# K-Diag_small-_single_small-multi2.net
KiCad netlist of a schematic drawn in EAGLE
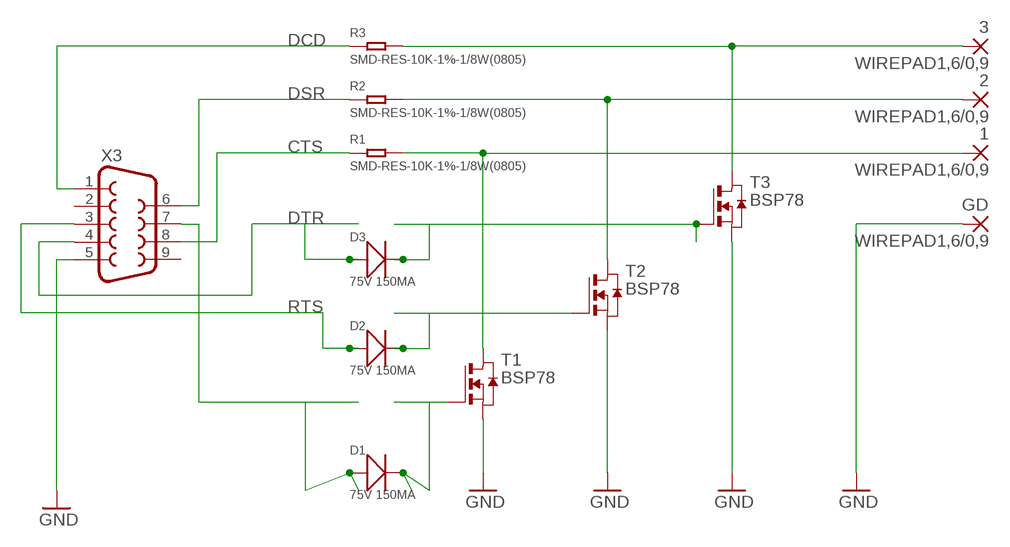
[diagram p0: schematic, sheet 1]
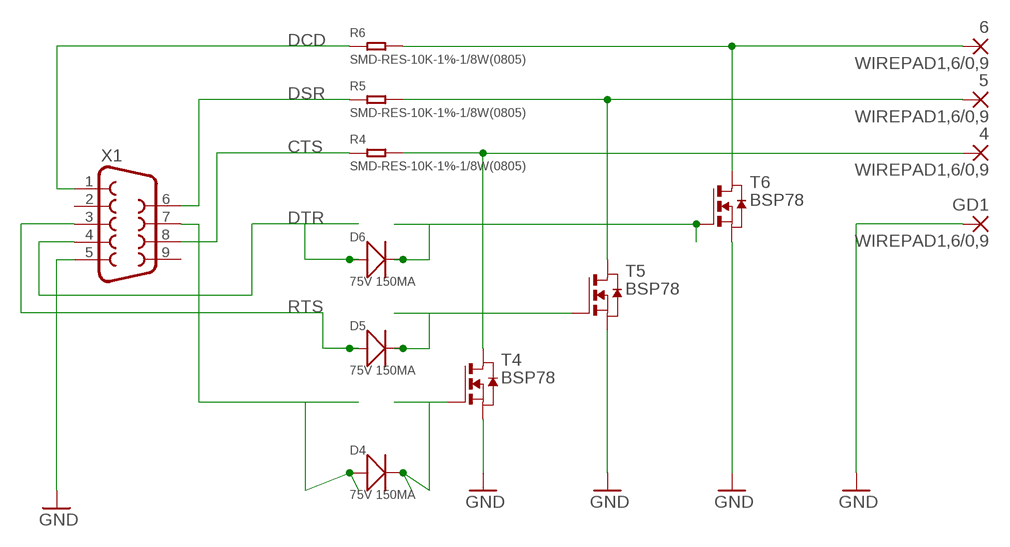
[diagram p1: schematic, sheet 2]
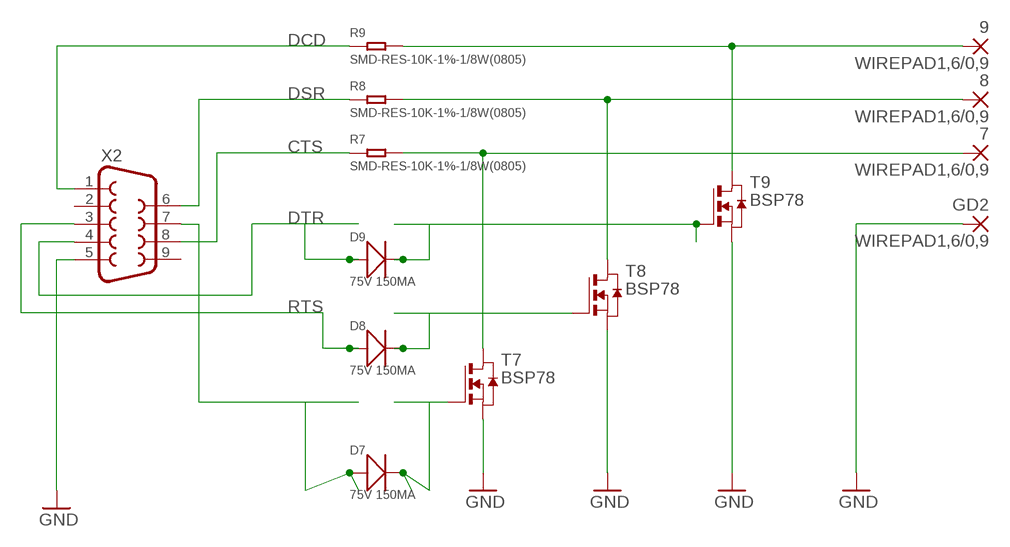
[diagram p2: schematic, sheet 3]
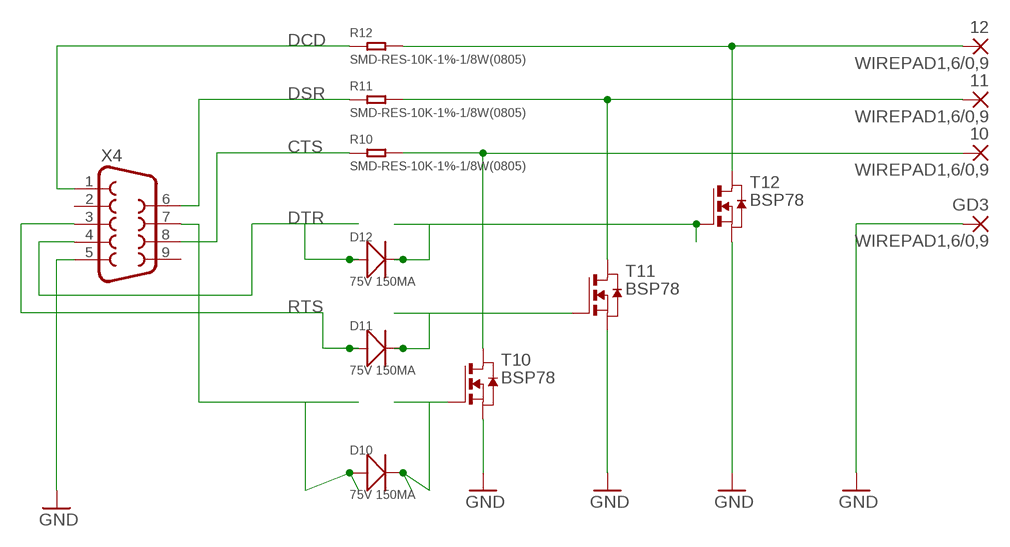
[diagram p3: schematic, sheet 4]
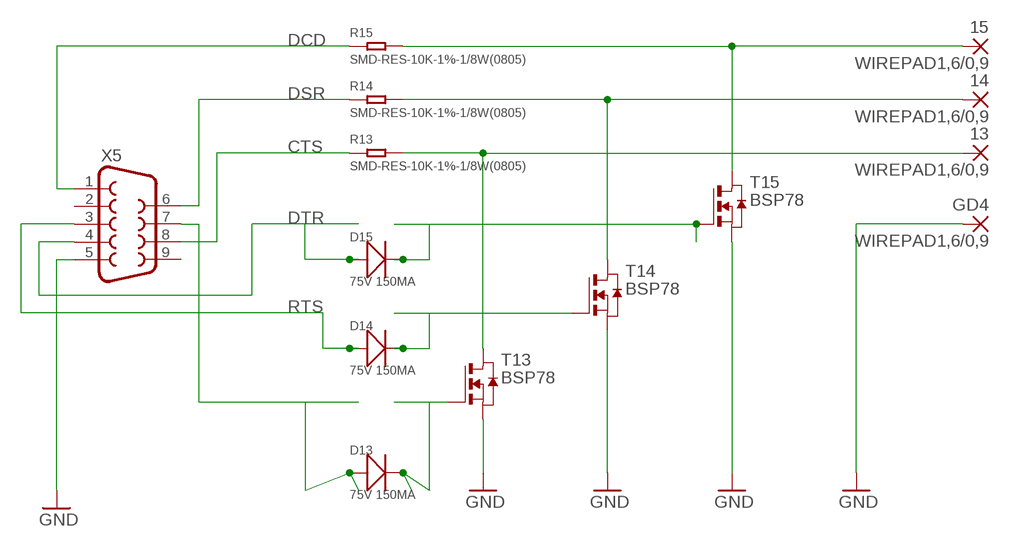
[diagram p4: schematic, sheet 5]
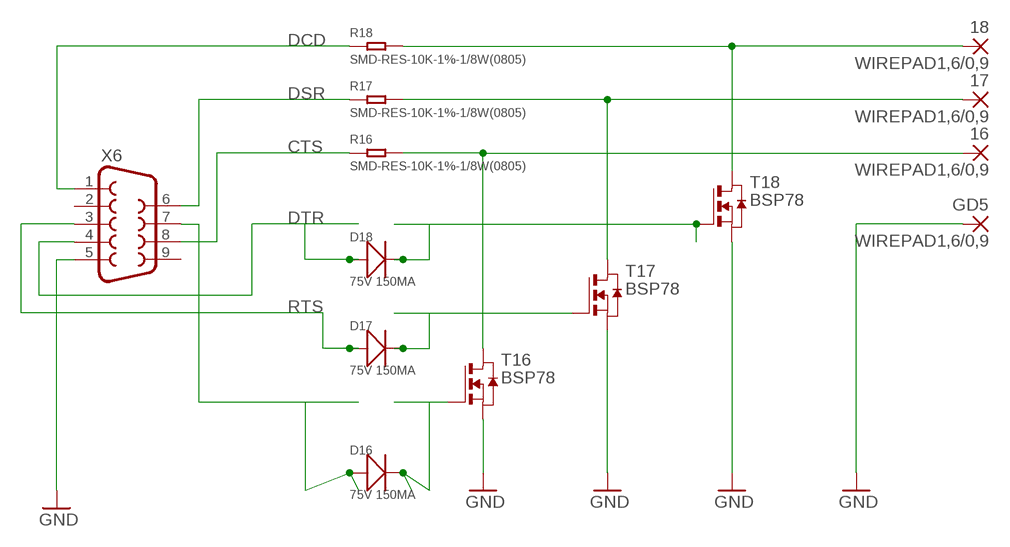
[diagram p5: schematic, sheet 6]
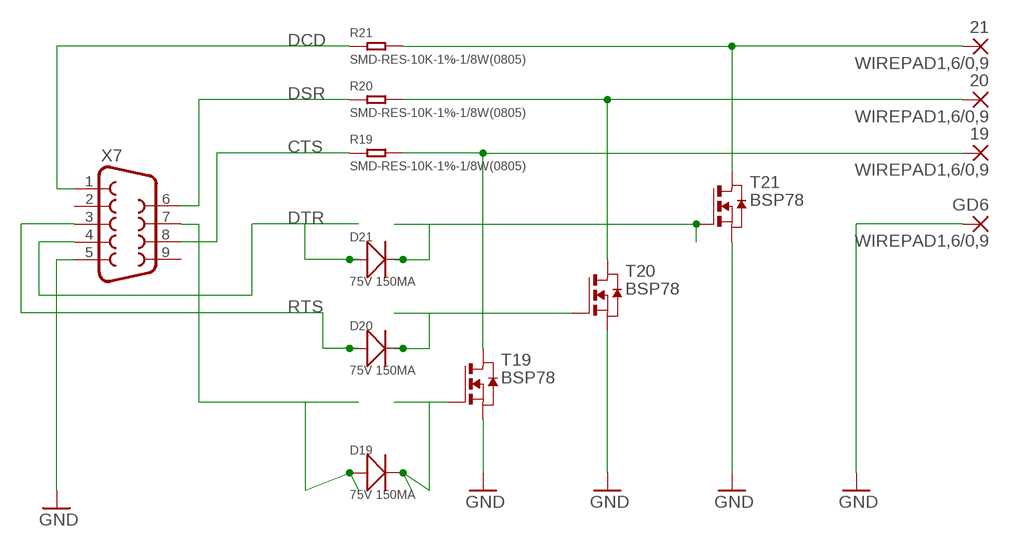
[diagram p6: schematic, sheet 7]
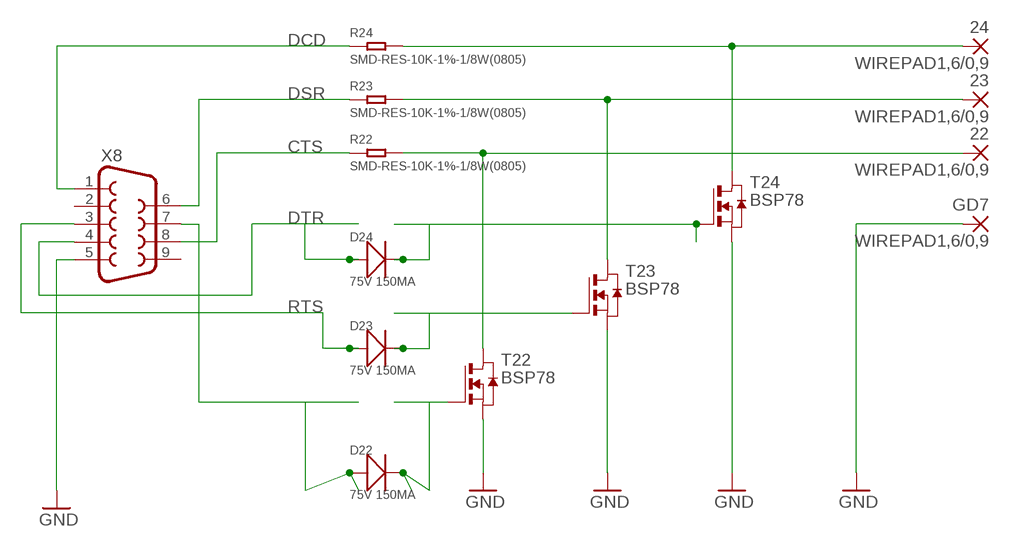
[diagram p7: schematic, sheet 8]
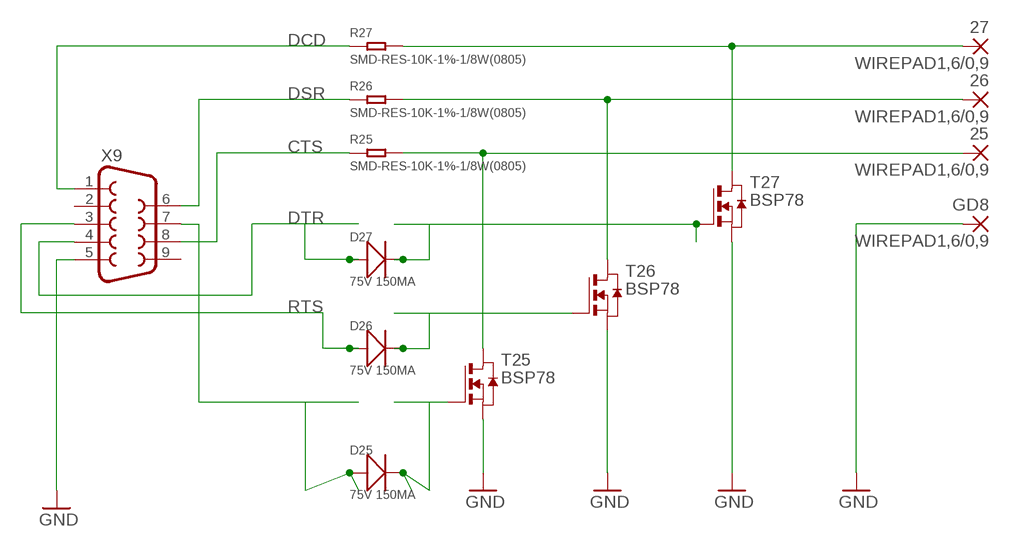
[diagram p8: schematic, sheet 9]

(export (version "E")
  (design (tool "Eeschema 10.0.6"))
  (components
    (comp (ref "4")
      (value "WIREPAD1,6/0,9")
      (footprint "eagle-import:1,6_0,9")
      (libsource (lib "eagle-import") (part "WIREPAD1,6/0,9"))
    )
    (comp (ref "5")
      (value "WIREPAD1,6/0,9")
      (footprint "eagle-import:1,6_0,9")
      (libsource (lib "eagle-import") (part "WIREPAD1,6/0,9"))
    )
    (comp (ref "6")
      (value "WIREPAD1,6/0,9")
      (footprint "eagle-import:1,6_0,9")
      (libsource (lib "eagle-import") (part "WIREPAD1,6/0,9"))
    )
    (comp (ref "D4")
      (value "75V 150MA")
      (footprint "eagle-import:LED-1206")
      (fields (field (name "MPN") "CD1206-S01575"))
      (libsource (lib "eagle-import") (part "SMD-DIODE-SWITCHING-75V-150MA(D1206)"))
    )
    (comp (ref "D5")
      (value "75V 150MA")
      (footprint "eagle-import:LED-1206")
      (fields (field (name "MPN") "CD1206-S01575"))
      (libsource (lib "eagle-import") (part "SMD-DIODE-SWITCHING-75V-150MA(D1206)"))
    )
    (comp (ref "D6")
      (value "75V 150MA")
      (footprint "eagle-import:LED-1206")
      (fields (field (name "MPN") "CD1206-S01575"))
      (libsource (lib "eagle-import") (part "SMD-DIODE-SWITCHING-75V-150MA(D1206)"))
    )
    (comp (ref "GD1")
      (value "WIREPAD1,6/0,9")
      (footprint "eagle-import:1,6_0,9")
      (libsource (lib "eagle-import") (part "WIREPAD1,6/0,9"))
    )
    (comp (ref "R4")
      (value "SMD-RES-10K-1%-1/8W(0805)")
      (footprint "eagle-import:R0805")
      (fields (field (name "MPN") "RC0805FR-0710KL"))
      (libsource (lib "eagle-import") (part "SMD-RES-10K-1%-1/8W(0805)"))
    )
    (comp (ref "R5")
      (value "SMD-RES-10K-1%-1/8W(0805)")
      (footprint "eagle-import:R0805")
      (fields (field (name "MPN") "RC0805FR-0710KL"))
      (libsource (lib "eagle-import") (part "SMD-RES-10K-1%-1/8W(0805)"))
    )
    (comp (ref "R6")
      (value "SMD-RES-10K-1%-1/8W(0805)")
      (footprint "eagle-import:R0805")
      (fields (field (name "MPN") "RC0805FR-0710KL"))
      (libsource (lib "eagle-import") (part "SMD-RES-10K-1%-1/8W(0805)"))
    )
    (comp (ref "T4")
      (value "BSP78")
      (footprint "eagle-import:SOT223")
      (libsource (lib "eagle-import") (part "NMOSSOT223"))
    )
    (comp (ref "T5")
      (value "BSP78")
      (footprint "eagle-import:SOT223")
      (libsource (lib "eagle-import") (part "NMOSSOT223"))
    )
    (comp (ref "T6")
      (value "BSP78")
      (footprint "eagle-import:SOT223")
      (libsource (lib "eagle-import") (part "NMOSSOT223"))
    )
    (comp (ref "X1")
      (value "F09D")
      (footprint "eagle-import:F09D")
      (libsource (lib "eagle-import") (part "F09D"))
    )
    (comp (ref "16")
      (value "WIREPAD1,6/0,9")
      (footprint "eagle-import:1,6_0,9")
      (libsource (lib "eagle-import") (part "WIREPAD1,6/0,9"))
    )
    (comp (ref "17")
      (value "WIREPAD1,6/0,9")
      (footprint "eagle-import:1,6_0,9")
      (libsource (lib "eagle-import") (part "WIREPAD1,6/0,9"))
    )
    (comp (ref "18")
      (value "WIREPAD1,6/0,9")
      (footprint "eagle-import:1,6_0,9")
      (libsource (lib "eagle-import") (part "WIREPAD1,6/0,9"))
    )
    (comp (ref "D16")
      (value "75V 150MA")
      (footprint "eagle-import:LED-1206")
      (fields (field (name "MPN") "CD1206-S01575"))
      (libsource (lib "eagle-import") (part "SMD-DIODE-SWITCHING-75V-150MA(D1206)"))
    )
    (comp (ref "D17")
      (value "75V 150MA")
      (footprint "eagle-import:LED-1206")
      (fields (field (name "MPN") "CD1206-S01575"))
      (libsource (lib "eagle-import") (part "SMD-DIODE-SWITCHING-75V-150MA(D1206)"))
    )
    (comp (ref "D18")
      (value "75V 150MA")
      (footprint "eagle-import:LED-1206")
      (fields (field (name "MPN") "CD1206-S01575"))
      (libsource (lib "eagle-import") (part "SMD-DIODE-SWITCHING-75V-150MA(D1206)"))
    )
    (comp (ref "GD5")
      (value "WIREPAD1,6/0,9")
      (footprint "eagle-import:1,6_0,9")
      (libsource (lib "eagle-import") (part "WIREPAD1,6/0,9"))
    )
    (comp (ref "R16")
      (value "SMD-RES-10K-1%-1/8W(0805)")
      (footprint "eagle-import:R0805")
      (fields (field (name "MPN") "RC0805FR-0710KL"))
      (libsource (lib "eagle-import") (part "SMD-RES-10K-1%-1/8W(0805)"))
    )
    (comp (ref "R17")
      (value "SMD-RES-10K-1%-1/8W(0805)")
      (footprint "eagle-import:R0805")
      (fields (field (name "MPN") "RC0805FR-0710KL"))
      (libsource (lib "eagle-import") (part "SMD-RES-10K-1%-1/8W(0805)"))
    )
    (comp (ref "R18")
      (value "SMD-RES-10K-1%-1/8W(0805)")
      (footprint "eagle-import:R0805")
      (fields (field (name "MPN") "RC0805FR-0710KL"))
      (libsource (lib "eagle-import") (part "SMD-RES-10K-1%-1/8W(0805)"))
    )
    (comp (ref "T16")
      (value "BSP78")
      (footprint "eagle-import:SOT223")
      (libsource (lib "eagle-import") (part "NMOSSOT223"))
    )
    (comp (ref "T17")
      (value "BSP78")
      (footprint "eagle-import:SOT223")
      (libsource (lib "eagle-import") (part "NMOSSOT223"))
    )
    (comp (ref "T18")
      (value "BSP78")
      (footprint "eagle-import:SOT223")
      (libsource (lib "eagle-import") (part "NMOSSOT223"))
    )
    (comp (ref "X6")
      (value "F09D")
      (footprint "eagle-import:F09D")
      (libsource (lib "eagle-import") (part "F09D"))
    )
    (comp (ref "13")
      (value "WIREPAD1,6/0,9")
      (footprint "eagle-import:1,6_0,9")
      (libsource (lib "eagle-import") (part "WIREPAD1,6/0,9"))
    )
    (comp (ref "14")
      (value "WIREPAD1,6/0,9")
      (footprint "eagle-import:1,6_0,9")
      (libsource (lib "eagle-import") (part "WIREPAD1,6/0,9"))
    )
    (comp (ref "15")
      (value "WIREPAD1,6/0,9")
      (footprint "eagle-import:1,6_0,9")
      (libsource (lib "eagle-import") (part "WIREPAD1,6/0,9"))
    )
    (comp (ref "D13")
      (value "75V 150MA")
      (footprint "eagle-import:LED-1206")
      (fields (field (name "MPN") "CD1206-S01575"))
      (libsource (lib "eagle-import") (part "SMD-DIODE-SWITCHING-75V-150MA(D1206)"))
    )
    (comp (ref "D14")
      (value "75V 150MA")
      (footprint "eagle-import:LED-1206")
      (fields (field (name "MPN") "CD1206-S01575"))
      (libsource (lib "eagle-import") (part "SMD-DIODE-SWITCHING-75V-150MA(D1206)"))
    )
    (comp (ref "D15")
      (value "75V 150MA")
      (footprint "eagle-import:LED-1206")
      (fields (field (name "MPN") "CD1206-S01575"))
      (libsource (lib "eagle-import") (part "SMD-DIODE-SWITCHING-75V-150MA(D1206)"))
    )
    (comp (ref "GD4")
      (value "WIREPAD1,6/0,9")
      (footprint "eagle-import:1,6_0,9")
      (libsource (lib "eagle-import") (part "WIREPAD1,6/0,9"))
    )
    (comp (ref "R13")
      (value "SMD-RES-10K-1%-1/8W(0805)")
      (footprint "eagle-import:R0805")
      (fields (field (name "MPN") "RC0805FR-0710KL"))
      (libsource (lib "eagle-import") (part "SMD-RES-10K-1%-1/8W(0805)"))
    )
    (comp (ref "R14")
      (value "SMD-RES-10K-1%-1/8W(0805)")
      (footprint "eagle-import:R0805")
      (fields (field (name "MPN") "RC0805FR-0710KL"))
      (libsource (lib "eagle-import") (part "SMD-RES-10K-1%-1/8W(0805)"))
    )
    (comp (ref "R15")
      (value "SMD-RES-10K-1%-1/8W(0805)")
      (footprint "eagle-import:R0805")
      (fields (field (name "MPN") "RC0805FR-0710KL"))
      (libsource (lib "eagle-import") (part "SMD-RES-10K-1%-1/8W(0805)"))
    )
    (comp (ref "T13")
      (value "BSP78")
      (footprint "eagle-import:SOT223")
      (libsource (lib "eagle-import") (part "NMOSSOT223"))
    )
    (comp (ref "T14")
      (value "BSP78")
      (footprint "eagle-import:SOT223")
      (libsource (lib "eagle-import") (part "NMOSSOT223"))
    )
    (comp (ref "T15")
      (value "BSP78")
      (footprint "eagle-import:SOT223")
      (libsource (lib "eagle-import") (part "NMOSSOT223"))
    )
    (comp (ref "X5")
      (value "F09D")
      (footprint "eagle-import:F09D")
      (libsource (lib "eagle-import") (part "F09D"))
    )
    (comp (ref "19")
      (value "WIREPAD1,6/0,9")
      (footprint "eagle-import:1,6_0,9")
      (libsource (lib "eagle-import") (part "WIREPAD1,6/0,9"))
    )
    (comp (ref "20")
      (value "WIREPAD1,6/0,9")
      (footprint "eagle-import:1,6_0,9")
      (libsource (lib "eagle-import") (part "WIREPAD1,6/0,9"))
    )
    (comp (ref "21")
      (value "WIREPAD1,6/0,9")
      (footprint "eagle-import:1,6_0,9")
      (libsource (lib "eagle-import") (part "WIREPAD1,6/0,9"))
    )
    (comp (ref "D19")
      (value "75V 150MA")
      (footprint "eagle-import:LED-1206")
      (fields (field (name "MPN") "CD1206-S01575"))
      (libsource (lib "eagle-import") (part "SMD-DIODE-SWITCHING-75V-150MA(D1206)"))
    )
    (comp (ref "D20")
      (value "75V 150MA")
      (footprint "eagle-import:LED-1206")
      (fields (field (name "MPN") "CD1206-S01575"))
      (libsource (lib "eagle-import") (part "SMD-DIODE-SWITCHING-75V-150MA(D1206)"))
    )
    (comp (ref "D21")
      (value "75V 150MA")
      (footprint "eagle-import:LED-1206")
      (fields (field (name "MPN") "CD1206-S01575"))
      (libsource (lib "eagle-import") (part "SMD-DIODE-SWITCHING-75V-150MA(D1206)"))
    )
    (comp (ref "GD6")
      (value "WIREPAD1,6/0,9")
      (footprint "eagle-import:1,6_0,9")
      (libsource (lib "eagle-import") (part "WIREPAD1,6/0,9"))
    )
    (comp (ref "R19")
      (value "SMD-RES-10K-1%-1/8W(0805)")
      (footprint "eagle-import:R0805")
      (fields (field (name "MPN") "RC0805FR-0710KL"))
      (libsource (lib "eagle-import") (part "SMD-RES-10K-1%-1/8W(0805)"))
    )
    (comp (ref "R20")
      (value "SMD-RES-10K-1%-1/8W(0805)")
      (footprint "eagle-import:R0805")
      (fields (field (name "MPN") "RC0805FR-0710KL"))
      (libsource (lib "eagle-import") (part "SMD-RES-10K-1%-1/8W(0805)"))
    )
    (comp (ref "R21")
      (value "SMD-RES-10K-1%-1/8W(0805)")
      (footprint "eagle-import:R0805")
      (fields (field (name "MPN") "RC0805FR-0710KL"))
      (libsource (lib "eagle-import") (part "SMD-RES-10K-1%-1/8W(0805)"))
    )
    (comp (ref "T19")
      (value "BSP78")
      (footprint "eagle-import:SOT223")
      (libsource (lib "eagle-import") (part "NMOSSOT223"))
    )
    (comp (ref "T20")
      (value "BSP78")
      (footprint "eagle-import:SOT223")
      (libsource (lib "eagle-import") (part "NMOSSOT223"))
    )
    (comp (ref "T21")
      (value "BSP78")
      (footprint "eagle-import:SOT223")
      (libsource (lib "eagle-import") (part "NMOSSOT223"))
    )
    (comp (ref "X7")
      (value "F09D")
      (footprint "eagle-import:F09D")
      (libsource (lib "eagle-import") (part "F09D"))
    )
    (comp (ref "25")
      (value "WIREPAD1,6/0,9")
      (footprint "eagle-import:1,6_0,9")
      (libsource (lib "eagle-import") (part "WIREPAD1,6/0,9"))
    )
    (comp (ref "26")
      (value "WIREPAD1,6/0,9")
      (footprint "eagle-import:1,6_0,9")
      (libsource (lib "eagle-import") (part "WIREPAD1,6/0,9"))
    )
    (comp (ref "27")
      (value "WIREPAD1,6/0,9")
      (footprint "eagle-import:1,6_0,9")
      (libsource (lib "eagle-import") (part "WIREPAD1,6/0,9"))
    )
    (comp (ref "D25")
      (value "75V 150MA")
      (footprint "eagle-import:LED-1206")
      (fields (field (name "MPN") "CD1206-S01575"))
      (libsource (lib "eagle-import") (part "SMD-DIODE-SWITCHING-75V-150MA(D1206)"))
    )
    (comp (ref "D26")
      (value "75V 150MA")
      (footprint "eagle-import:LED-1206")
      (fields (field (name "MPN") "CD1206-S01575"))
      (libsource (lib "eagle-import") (part "SMD-DIODE-SWITCHING-75V-150MA(D1206)"))
    )
    (comp (ref "D27")
      (value "75V 150MA")
      (footprint "eagle-import:LED-1206")
      (fields (field (name "MPN") "CD1206-S01575"))
      (libsource (lib "eagle-import") (part "SMD-DIODE-SWITCHING-75V-150MA(D1206)"))
    )
    (comp (ref "GD8")
      (value "WIREPAD1,6/0,9")
      (footprint "eagle-import:1,6_0,9")
      (libsource (lib "eagle-import") (part "WIREPAD1,6/0,9"))
    )
    (comp (ref "R25")
      (value "SMD-RES-10K-1%-1/8W(0805)")
      (footprint "eagle-import:R0805")
      (fields (field (name "MPN") "RC0805FR-0710KL"))
      (libsource (lib "eagle-import") (part "SMD-RES-10K-1%-1/8W(0805)"))
    )
    (comp (ref "R26")
      (value "SMD-RES-10K-1%-1/8W(0805)")
      (footprint "eagle-import:R0805")
      (fields (field (name "MPN") "RC0805FR-0710KL"))
      (libsource (lib "eagle-import") (part "SMD-RES-10K-1%-1/8W(0805)"))
    )
    (comp (ref "R27")
      (value "SMD-RES-10K-1%-1/8W(0805)")
      (footprint "eagle-import:R0805")
      (fields (field (name "MPN") "RC0805FR-0710KL"))
      (libsource (lib "eagle-import") (part "SMD-RES-10K-1%-1/8W(0805)"))
    )
    (comp (ref "T25")
      (value "BSP78")
      (footprint "eagle-import:SOT223")
      (libsource (lib "eagle-import") (part "NMOSSOT223"))
    )
    (comp (ref "T26")
      (value "BSP78")
      (footprint "eagle-import:SOT223")
      (libsource (lib "eagle-import") (part "NMOSSOT223"))
    )
    (comp (ref "T27")
      (value "BSP78")
      (footprint "eagle-import:SOT223")
      (libsource (lib "eagle-import") (part "NMOSSOT223"))
    )
    (comp (ref "X9")
      (value "F09D")
      (footprint "eagle-import:F09D")
      (libsource (lib "eagle-import") (part "F09D"))
    )
    (comp (ref "10")
      (value "WIREPAD1,6/0,9")
      (footprint "eagle-import:1,6_0,9")
      (libsource (lib "eagle-import") (part "WIREPAD1,6/0,9"))
    )
    (comp (ref "11")
      (value "WIREPAD1,6/0,9")
      (footprint "eagle-import:1,6_0,9")
      (libsource (lib "eagle-import") (part "WIREPAD1,6/0,9"))
    )
    (comp (ref "12")
      (value "WIREPAD1,6/0,9")
      (footprint "eagle-import:1,6_0,9")
      (libsource (lib "eagle-import") (part "WIREPAD1,6/0,9"))
    )
    (comp (ref "D10")
      (value "75V 150MA")
      (footprint "eagle-import:LED-1206")
      (fields (field (name "MPN") "CD1206-S01575"))
      (libsource (lib "eagle-import") (part "SMD-DIODE-SWITCHING-75V-150MA(D1206)"))
    )
    (comp (ref "D11")
      (value "75V 150MA")
      (footprint "eagle-import:LED-1206")
      (fields (field (name "MPN") "CD1206-S01575"))
      (libsource (lib "eagle-import") (part "SMD-DIODE-SWITCHING-75V-150MA(D1206)"))
    )
    (comp (ref "D12")
      (value "75V 150MA")
      (footprint "eagle-import:LED-1206")
      (fields (field (name "MPN") "CD1206-S01575"))
      (libsource (lib "eagle-import") (part "SMD-DIODE-SWITCHING-75V-150MA(D1206)"))
    )
    (comp (ref "GD3")
      (value "WIREPAD1,6/0,9")
      (footprint "eagle-import:1,6_0,9")
      (libsource (lib "eagle-import") (part "WIREPAD1,6/0,9"))
    )
    (comp (ref "R10")
      (value "SMD-RES-10K-1%-1/8W(0805)")
      (footprint "eagle-import:R0805")
      (fields (field (name "MPN") "RC0805FR-0710KL"))
      (libsource (lib "eagle-import") (part "SMD-RES-10K-1%-1/8W(0805)"))
    )
    (comp (ref "R11")
      (value "SMD-RES-10K-1%-1/8W(0805)")
      (footprint "eagle-import:R0805")
      (fields (field (name "MPN") "RC0805FR-0710KL"))
      (libsource (lib "eagle-import") (part "SMD-RES-10K-1%-1/8W(0805)"))
    )
    (comp (ref "R12")
      (value "SMD-RES-10K-1%-1/8W(0805)")
      (footprint "eagle-import:R0805")
      (fields (field (name "MPN") "RC0805FR-0710KL"))
      (libsource (lib "eagle-import") (part "SMD-RES-10K-1%-1/8W(0805)"))
    )
    (comp (ref "T10")
      (value "BSP78")
      (footprint "eagle-import:SOT223")
      (libsource (lib "eagle-import") (part "NMOSSOT223"))
    )
    (comp (ref "T11")
      (value "BSP78")
      (footprint "eagle-import:SOT223")
      (libsource (lib "eagle-import") (part "NMOSSOT223"))
    )
    (comp (ref "T12")
      (value "BSP78")
      (footprint "eagle-import:SOT223")
      (libsource (lib "eagle-import") (part "NMOSSOT223"))
    )
    (comp (ref "X4")
      (value "F09D")
      (footprint "eagle-import:F09D")
      (libsource (lib "eagle-import") (part "F09D"))
    )
    (comp (ref "22")
      (value "WIREPAD1,6/0,9")
      (footprint "eagle-import:1,6_0,9")
      (libsource (lib "eagle-import") (part "WIREPAD1,6/0,9"))
    )
    (comp (ref "23")
      (value "WIREPAD1,6/0,9")
      (footprint "eagle-import:1,6_0,9")
      (libsource (lib "eagle-import") (part "WIREPAD1,6/0,9"))
    )
    (comp (ref "24")
      (value "WIREPAD1,6/0,9")
      (footprint "eagle-import:1,6_0,9")
      (libsource (lib "eagle-import") (part "WIREPAD1,6/0,9"))
    )
    (comp (ref "D22")
      (value "75V 150MA")
      (footprint "eagle-import:LED-1206")
      (fields (field (name "MPN") "CD1206-S01575"))
      (libsource (lib "eagle-import") (part "SMD-DIODE-SWITCHING-75V-150MA(D1206)"))
    )
    (comp (ref "D23")
      (value "75V 150MA")
      (footprint "eagle-import:LED-1206")
      (fields (field (name "MPN") "CD1206-S01575"))
      (libsource (lib "eagle-import") (part "SMD-DIODE-SWITCHING-75V-150MA(D1206)"))
    )
    (comp (ref "D24")
      (value "75V 150MA")
      (footprint "eagle-import:LED-1206")
      (fields (field (name "MPN") "CD1206-S01575"))
      (libsource (lib "eagle-import") (part "SMD-DIODE-SWITCHING-75V-150MA(D1206)"))
    )
    (comp (ref "GD7")
      (value "WIREPAD1,6/0,9")
      (footprint "eagle-import:1,6_0,9")
      (libsource (lib "eagle-import") (part "WIREPAD1,6/0,9"))
    )
    (comp (ref "R22")
      (value "SMD-RES-10K-1%-1/8W(0805)")
      (footprint "eagle-import:R0805")
      (fields (field (name "MPN") "RC0805FR-0710KL"))
      (libsource (lib "eagle-import") (part "SMD-RES-10K-1%-1/8W(0805)"))
    )
    (comp (ref "R23")
      (value "SMD-RES-10K-1%-1/8W(0805)")
      (footprint "eagle-import:R0805")
      (fields (field (name "MPN") "RC0805FR-0710KL"))
      (libsource (lib "eagle-import") (part "SMD-RES-10K-1%-1/8W(0805)"))
    )
    (comp (ref "R24")
      (value "SMD-RES-10K-1%-1/8W(0805)")
      (footprint "eagle-import:R0805")
      (fields (field (name "MPN") "RC0805FR-0710KL"))
      (libsource (lib "eagle-import") (part "SMD-RES-10K-1%-1/8W(0805)"))
    )
    (comp (ref "T22")
      (value "BSP78")
      (footprint "eagle-import:SOT223")
      (libsource (lib "eagle-import") (part "NMOSSOT223"))
    )
    (comp (ref "T23")
      (value "BSP78")
      (footprint "eagle-import:SOT223")
      (libsource (lib "eagle-import") (part "NMOSSOT223"))
    )
    (comp (ref "T24")
      (value "BSP78")
      (footprint "eagle-import:SOT223")
      (libsource (lib "eagle-import") (part "NMOSSOT223"))
    )
    (comp (ref "X8")
      (value "F09D")
      (footprint "eagle-import:F09D")
      (libsource (lib "eagle-import") (part "F09D"))
    )
    (comp (ref "7")
      (value "WIREPAD1,6/0,9")
      (footprint "eagle-import:1,6_0,9")
      (libsource (lib "eagle-import") (part "WIREPAD1,6/0,9"))
    )
    (comp (ref "8")
      (value "WIREPAD1,6/0,9")
      (footprint "eagle-import:1,6_0,9")
      (libsource (lib "eagle-import") (part "WIREPAD1,6/0,9"))
    )
    (comp (ref "9")
      (value "WIREPAD1,6/0,9")
      (footprint "eagle-import:1,6_0,9")
      (libsource (lib "eagle-import") (part "WIREPAD1,6/0,9"))
    )
    (comp (ref "D7")
      (value "75V 150MA")
      (footprint "eagle-import:LED-1206")
      (fields (field (name "MPN") "CD1206-S01575"))
      (libsource (lib "eagle-import") (part "SMD-DIODE-SWITCHING-75V-150MA(D1206)"))
    )
    (comp (ref "D8")
      (value "75V 150MA")
      (footprint "eagle-import:LED-1206")
      (fields (field (name "MPN") "CD1206-S01575"))
      (libsource (lib "eagle-import") (part "SMD-DIODE-SWITCHING-75V-150MA(D1206)"))
    )
    (comp (ref "D9")
      (value "75V 150MA")
      (footprint "eagle-import:LED-1206")
      (fields (field (name "MPN") "CD1206-S01575"))
      (libsource (lib "eagle-import") (part "SMD-DIODE-SWITCHING-75V-150MA(D1206)"))
    )
    (comp (ref "GD2")
      (value "WIREPAD1,6/0,9")
      (footprint "eagle-import:1,6_0,9")
      (libsource (lib "eagle-import") (part "WIREPAD1,6/0,9"))
    )
    (comp (ref "R7")
      (value "SMD-RES-10K-1%-1/8W(0805)")
      (footprint "eagle-import:R0805")
      (fields (field (name "MPN") "RC0805FR-0710KL"))
      (libsource (lib "eagle-import") (part "SMD-RES-10K-1%-1/8W(0805)"))
    )
    (comp (ref "R8")
      (value "SMD-RES-10K-1%-1/8W(0805)")
      (footprint "eagle-import:R0805")
      (fields (field (name "MPN") "RC0805FR-0710KL"))
      (libsource (lib "eagle-import") (part "SMD-RES-10K-1%-1/8W(0805)"))
    )
    (comp (ref "R9")
      (value "SMD-RES-10K-1%-1/8W(0805)")
      (footprint "eagle-import:R0805")
      (fields (field (name "MPN") "RC0805FR-0710KL"))
      (libsource (lib "eagle-import") (part "SMD-RES-10K-1%-1/8W(0805)"))
    )
    (comp (ref "T7")
      (value "BSP78")
      (footprint "eagle-import:SOT223")
      (libsource (lib "eagle-import") (part "NMOSSOT223"))
    )
    (comp (ref "T8")
      (value "BSP78")
      (footprint "eagle-import:SOT223")
      (libsource (lib "eagle-import") (part "NMOSSOT223"))
    )
    (comp (ref "T9")
      (value "BSP78")
      (footprint "eagle-import:SOT223")
      (libsource (lib "eagle-import") (part "NMOSSOT223"))
    )
    (comp (ref "X2")
      (value "F09D")
      (footprint "eagle-import:F09D")
      (libsource (lib "eagle-import") (part "F09D"))
    )
    (comp (ref "1")
      (value "WIREPAD1,6/0,9")
      (footprint "eagle-import:1,6_0,9")
      (libsource (lib "eagle-import") (part "WIREPAD1,6/0,9"))
    )
    (comp (ref "2")
      (value "WIREPAD1,6/0,9")
      (footprint "eagle-import:1,6_0,9")
      (libsource (lib "eagle-import") (part "WIREPAD1,6/0,9"))
    )
    (comp (ref "3")
      (value "WIREPAD1,6/0,9")
      (footprint "eagle-import:1,6_0,9")
      (libsource (lib "eagle-import") (part "WIREPAD1,6/0,9"))
    )
    (comp (ref "D1")
      (value "75V 150MA")
      (footprint "eagle-import:LED-1206")
      (fields (field (name "MPN") "CD1206-S01575"))
      (libsource (lib "eagle-import") (part "SMD-DIODE-SWITCHING-75V-150MA(D1206)"))
    )
    (comp (ref "D2")
      (value "75V 150MA")
      (footprint "eagle-import:LED-1206")
      (fields (field (name "MPN") "CD1206-S01575"))
      (libsource (lib "eagle-import") (part "SMD-DIODE-SWITCHING-75V-150MA(D1206)"))
    )
    (comp (ref "D3")
      (value "75V 150MA")
      (footprint "eagle-import:LED-1206")
      (fields (field (name "MPN") "CD1206-S01575"))
      (libsource (lib "eagle-import") (part "SMD-DIODE-SWITCHING-75V-150MA(D1206)"))
    )
    (comp (ref "GD")
      (value "WIREPAD1,6/0,9")
      (footprint "eagle-import:1,6_0,9")
      (libsource (lib "eagle-import") (part "WIREPAD1,6/0,9"))
    )
    (comp (ref "R1")
      (value "SMD-RES-10K-1%-1/8W(0805)")
      (footprint "eagle-import:R0805")
      (fields (field (name "MPN") "RC0805FR-0710KL"))
      (libsource (lib "eagle-import") (part "SMD-RES-10K-1%-1/8W(0805)"))
    )
    (comp (ref "R2")
      (value "SMD-RES-10K-1%-1/8W(0805)")
      (footprint "eagle-import:R0805")
      (fields (field (name "MPN") "RC0805FR-0710KL"))
      (libsource (lib "eagle-import") (part "SMD-RES-10K-1%-1/8W(0805)"))
    )
    (comp (ref "R3")
      (value "SMD-RES-10K-1%-1/8W(0805)")
      (footprint "eagle-import:R0805")
      (fields (field (name "MPN") "RC0805FR-0710KL"))
      (libsource (lib "eagle-import") (part "SMD-RES-10K-1%-1/8W(0805)"))
    )
    (comp (ref "T1")
      (value "BSP78")
      (footprint "eagle-import:SOT223")
      (libsource (lib "eagle-import") (part "NMOSSOT223"))
    )
    (comp (ref "T2")
      (value "BSP78")
      (footprint "eagle-import:SOT223")
      (libsource (lib "eagle-import") (part "NMOSSOT223"))
    )
    (comp (ref "T3")
      (value "BSP78")
      (footprint "eagle-import:SOT223")
      (libsource (lib "eagle-import") (part "NMOSSOT223"))
    )
    (comp (ref "X3")
      (value "F09D")
      (footprint "eagle-import:F09D")
      (libsource (lib "eagle-import") (part "F09D"))
    )
  )
  (nets
    (net (code "1") (name "CTS") (class "Default")
      (node (ref "R1") (pin "1") (pinfunction "1_1") (pintype "passive"))
      (node (ref "R10") (pin "1") (pinfunction "1_1") (pintype "passive"))
      (node (ref "R13") (pin "1") (pinfunction "1_1") (pintype "passive"))
      (node (ref "R16") (pin "1") (pinfunction "1_1") (pintype "passive"))
      (node (ref "R19") (pin "1") (pinfunction "1_1") (pintype "passive"))
      (node (ref "R22") (pin "1") (pinfunction "1_1") (pintype "passive"))
      (node (ref "R25") (pin "1") (pinfunction "1_1") (pintype "passive"))
      (node (ref "R4") (pin "1") (pinfunction "1_1") (pintype "passive"))
      (node (ref "R7") (pin "1") (pinfunction "1_1") (pintype "passive"))
      (node (ref "X1") (pin "8") (pinfunction "8_8") (pintype "passive"))
      (node (ref "X2") (pin "8") (pinfunction "8_8") (pintype "passive"))
      (node (ref "X3") (pin "8") (pinfunction "8_8") (pintype "passive"))
      (node (ref "X4") (pin "8") (pinfunction "8_8") (pintype "passive"))
      (node (ref "X5") (pin "8") (pinfunction "8_8") (pintype "passive"))
      (node (ref "X6") (pin "8") (pinfunction "8_8") (pintype "passive"))
      (node (ref "X7") (pin "8") (pinfunction "8_8") (pintype "passive"))
      (node (ref "X8") (pin "8") (pinfunction "8_8") (pintype "passive"))
      (node (ref "X9") (pin "8") (pinfunction "8_8") (pintype "passive"))
    )
    (net (code "2") (name "DCD") (class "Default")
      (node (ref "R12") (pin "1") (pinfunction "1_1") (pintype "passive"))
      (node (ref "R15") (pin "1") (pinfunction "1_1") (pintype "passive"))
      (node (ref "R18") (pin "1") (pinfunction "1_1") (pintype "passive"))
      (node (ref "R21") (pin "1") (pinfunction "1_1") (pintype "passive"))
      (node (ref "R24") (pin "1") (pinfunction "1_1") (pintype "passive"))
      (node (ref "R27") (pin "1") (pinfunction "1_1") (pintype "passive"))
      (node (ref "R3") (pin "1") (pinfunction "1_1") (pintype "passive"))
      (node (ref "R6") (pin "1") (pinfunction "1_1") (pintype "passive"))
      (node (ref "R9") (pin "1") (pinfunction "1_1") (pintype "passive"))
      (node (ref "X1") (pin "1") (pinfunction "1_1") (pintype "passive"))
      (node (ref "X2") (pin "1") (pinfunction "1_1") (pintype "passive"))
      (node (ref "X3") (pin "1") (pinfunction "1_1") (pintype "passive"))
      (node (ref "X4") (pin "1") (pinfunction "1_1") (pintype "passive"))
      (node (ref "X5") (pin "1") (pinfunction "1_1") (pintype "passive"))
      (node (ref "X6") (pin "1") (pinfunction "1_1") (pintype "passive"))
      (node (ref "X7") (pin "1") (pinfunction "1_1") (pintype "passive"))
      (node (ref "X8") (pin "1") (pinfunction "1_1") (pintype "passive"))
      (node (ref "X9") (pin "1") (pinfunction "1_1") (pintype "passive"))
    )
    (net (code "3") (name "DSR") (class "Default")
      (node (ref "R11") (pin "1") (pinfunction "1_1") (pintype "passive"))
      (node (ref "R14") (pin "1") (pinfunction "1_1") (pintype "passive"))
      (node (ref "R17") (pin "1") (pinfunction "1_1") (pintype "passive"))
      (node (ref "R2") (pin "1") (pinfunction "1_1") (pintype "passive"))
      (node (ref "R20") (pin "1") (pinfunction "1_1") (pintype "passive"))
      (node (ref "R23") (pin "1") (pinfunction "1_1") (pintype "passive"))
      (node (ref "R26") (pin "1") (pinfunction "1_1") (pintype "passive"))
      (node (ref "R5") (pin "1") (pinfunction "1_1") (pintype "passive"))
      (node (ref "R8") (pin "1") (pinfunction "1_1") (pintype "passive"))
      (node (ref "X1") (pin "6") (pinfunction "6_6") (pintype "passive"))
      (node (ref "X2") (pin "6") (pinfunction "6_6") (pintype "passive"))
      (node (ref "X3") (pin "6") (pinfunction "6_6") (pintype "passive"))
      (node (ref "X4") (pin "6") (pinfunction "6_6") (pintype "passive"))
      (node (ref "X5") (pin "6") (pinfunction "6_6") (pintype "passive"))
      (node (ref "X6") (pin "6") (pinfunction "6_6") (pintype "passive"))
      (node (ref "X7") (pin "6") (pinfunction "6_6") (pintype "passive"))
      (node (ref "X8") (pin "6") (pinfunction "6_6") (pintype "passive"))
      (node (ref "X9") (pin "6") (pinfunction "6_6") (pintype "passive"))
    )
    (net (code "4") (name "DTR") (class "Default")
      (node (ref "D12") (pin "+") (pinfunction "+_+") (pintype "passive"))
      (node (ref "D15") (pin "+") (pinfunction "+_+") (pintype "passive"))
      (node (ref "D18") (pin "+") (pinfunction "+_+") (pintype "passive"))
      (node (ref "D21") (pin "+") (pinfunction "+_+") (pintype "passive"))
      (node (ref "D24") (pin "+") (pinfunction "+_+") (pintype "passive"))
      (node (ref "D27") (pin "+") (pinfunction "+_+") (pintype "passive"))
      (node (ref "D3") (pin "+") (pinfunction "+_+") (pintype "passive"))
      (node (ref "D6") (pin "+") (pinfunction "+_+") (pintype "passive"))
      (node (ref "D9") (pin "+") (pinfunction "+_+") (pintype "passive"))
      (node (ref "X1") (pin "4") (pinfunction "4_4") (pintype "passive"))
      (node (ref "X2") (pin "4") (pinfunction "4_4") (pintype "passive"))
      (node (ref "X3") (pin "4") (pinfunction "4_4") (pintype "passive"))
      (node (ref "X4") (pin "4") (pinfunction "4_4") (pintype "passive"))
      (node (ref "X5") (pin "4") (pinfunction "4_4") (pintype "passive"))
      (node (ref "X6") (pin "4") (pinfunction "4_4") (pintype "passive"))
      (node (ref "X7") (pin "4") (pinfunction "4_4") (pintype "passive"))
      (node (ref "X8") (pin "4") (pinfunction "4_4") (pintype "passive"))
      (node (ref "X9") (pin "4") (pinfunction "4_4") (pintype "passive"))
    )
    (net (code "5") (name "GND") (class "Default")
      (node (ref "GD") (pin "1") (pinfunction "P_1") (pintype "passive"))
      (node (ref "GD1") (pin "1") (pinfunction "P_1") (pintype "passive"))
      (node (ref "GD2") (pin "1") (pinfunction "P_1") (pintype "passive"))
      (node (ref "GD3") (pin "1") (pinfunction "P_1") (pintype "passive"))
      (node (ref "GD4") (pin "1") (pinfunction "P_1") (pintype "passive"))
      (node (ref "GD5") (pin "1") (pinfunction "P_1") (pintype "passive"))
      (node (ref "GD6") (pin "1") (pinfunction "P_1") (pintype "passive"))
      (node (ref "GD7") (pin "1") (pinfunction "P_1") (pintype "passive"))
      (node (ref "GD8") (pin "1") (pinfunction "P_1") (pintype "passive"))
      (node (ref "T1") (pin "3") (pinfunction "S_3") (pintype "passive"))
      (node (ref "T10") (pin "3") (pinfunction "S_3") (pintype "passive"))
      (node (ref "T11") (pin "3") (pinfunction "S_3") (pintype "passive"))
      (node (ref "T12") (pin "3") (pinfunction "S_3") (pintype "passive"))
      (node (ref "T13") (pin "3") (pinfunction "S_3") (pintype "passive"))
      (node (ref "T14") (pin "3") (pinfunction "S_3") (pintype "passive"))
      (node (ref "T15") (pin "3") (pinfunction "S_3") (pintype "passive"))
      (node (ref "T16") (pin "3") (pinfunction "S_3") (pintype "passive"))
      (node (ref "T17") (pin "3") (pinfunction "S_3") (pintype "passive"))
      (node (ref "T18") (pin "3") (pinfunction "S_3") (pintype "passive"))
      (node (ref "T19") (pin "3") (pinfunction "S_3") (pintype "passive"))
      (node (ref "T2") (pin "3") (pinfunction "S_3") (pintype "passive"))
      (node (ref "T20") (pin "3") (pinfunction "S_3") (pintype "passive"))
      (node (ref "T21") (pin "3") (pinfunction "S_3") (pintype "passive"))
      (node (ref "T22") (pin "3") (pinfunction "S_3") (pintype "passive"))
      (node (ref "T23") (pin "3") (pinfunction "S_3") (pintype "passive"))
      (node (ref "T24") (pin "3") (pinfunction "S_3") (pintype "passive"))
      (node (ref "T25") (pin "3") (pinfunction "S_3") (pintype "passive"))
      (node (ref "T26") (pin "3") (pinfunction "S_3") (pintype "passive"))
      (node (ref "T27") (pin "3") (pinfunction "S_3") (pintype "passive"))
      (node (ref "T3") (pin "3") (pinfunction "S_3") (pintype "passive"))
      (node (ref "T4") (pin "3") (pinfunction "S_3") (pintype "passive"))
      (node (ref "T5") (pin "3") (pinfunction "S_3") (pintype "passive"))
      (node (ref "T6") (pin "3") (pinfunction "S_3") (pintype "passive"))
      (node (ref "T7") (pin "3") (pinfunction "S_3") (pintype "passive"))
      (node (ref "T8") (pin "3") (pinfunction "S_3") (pintype "passive"))
      (node (ref "T9") (pin "3") (pinfunction "S_3") (pintype "passive"))
      (node (ref "X1") (pin "5") (pinfunction "5_5") (pintype "passive"))
      (node (ref "X2") (pin "5") (pinfunction "5_5") (pintype "passive"))
      (node (ref "X3") (pin "5") (pinfunction "5_5") (pintype "passive"))
      (node (ref "X4") (pin "5") (pinfunction "5_5") (pintype "passive"))
      (node (ref "X5") (pin "5") (pinfunction "5_5") (pintype "passive"))
      (node (ref "X6") (pin "5") (pinfunction "5_5") (pintype "passive"))
      (node (ref "X7") (pin "5") (pinfunction "5_5") (pintype "passive"))
      (node (ref "X8") (pin "5") (pinfunction "5_5") (pintype "passive"))
      (node (ref "X9") (pin "5") (pinfunction "5_5") (pintype "passive"))
    )
    (net (code "6") (name "Net-(1-P)") (class "Default")
      (node (ref "1") (pin "1") (pinfunction "P_1") (pintype "passive"))
      (node (ref "R1") (pin "2") (pinfunction "2_2") (pintype "passive"))
      (node (ref "T1") (pin "2") (pinfunction "D_2") (pintype "passive"))
      (node (ref "T1") (pin "4") (pinfunction "D_4") (pintype "passive"))
    )
    (net (code "7") (name "Net-(2-P)") (class "Default")
      (node (ref "2") (pin "1") (pinfunction "P_1") (pintype "passive"))
      (node (ref "R2") (pin "2") (pinfunction "2_2") (pintype "passive"))
      (node (ref "T2") (pin "2") (pinfunction "D_2") (pintype "passive"))
      (node (ref "T2") (pin "4") (pinfunction "D_4") (pintype "passive"))
    )
    (net (code "8") (name "Net-(3-P)") (class "Default")
      (node (ref "3") (pin "1") (pinfunction "P_1") (pintype "passive"))
      (node (ref "R3") (pin "2") (pinfunction "2_2") (pintype "passive"))
      (node (ref "T3") (pin "2") (pinfunction "D_2") (pintype "passive"))
      (node (ref "T3") (pin "4") (pinfunction "D_4") (pintype "passive"))
    )
    (net (code "9") (name "Net-(4-P)") (class "Default")
      (node (ref "4") (pin "1") (pinfunction "P_1") (pintype "passive"))
      (node (ref "R4") (pin "2") (pinfunction "2_2") (pintype "passive"))
      (node (ref "T4") (pin "2") (pinfunction "D_2") (pintype "passive"))
      (node (ref "T4") (pin "4") (pinfunction "D_4") (pintype "passive"))
    )
    (net (code "10") (name "Net-(5-P)") (class "Default")
      (node (ref "5") (pin "1") (pinfunction "P_1") (pintype "passive"))
      (node (ref "R5") (pin "2") (pinfunction "2_2") (pintype "passive"))
      (node (ref "T5") (pin "2") (pinfunction "D_2") (pintype "passive"))
      (node (ref "T5") (pin "4") (pinfunction "D_4") (pintype "passive"))
    )
    (net (code "11") (name "Net-(6-P)") (class "Default")
      (node (ref "6") (pin "1") (pinfunction "P_1") (pintype "passive"))
      (node (ref "R6") (pin "2") (pinfunction "2_2") (pintype "passive"))
      (node (ref "T6") (pin "2") (pinfunction "D_2") (pintype "passive"))
      (node (ref "T6") (pin "4") (pinfunction "D_4") (pintype "passive"))
    )
    (net (code "12") (name "Net-(7-P)") (class "Default")
      (node (ref "7") (pin "1") (pinfunction "P_1") (pintype "passive"))
      (node (ref "R7") (pin "2") (pinfunction "2_2") (pintype "passive"))
      (node (ref "T7") (pin "2") (pinfunction "D_2") (pintype "passive"))
      (node (ref "T7") (pin "4") (pinfunction "D_4") (pintype "passive"))
    )
    (net (code "13") (name "Net-(8-P)") (class "Default")
      (node (ref "8") (pin "1") (pinfunction "P_1") (pintype "passive"))
      (node (ref "R8") (pin "2") (pinfunction "2_2") (pintype "passive"))
      (node (ref "T8") (pin "2") (pinfunction "D_2") (pintype "passive"))
      (node (ref "T8") (pin "4") (pinfunction "D_4") (pintype "passive"))
    )
    (net (code "14") (name "Net-(9-P)") (class "Default")
      (node (ref "9") (pin "1") (pinfunction "P_1") (pintype "passive"))
      (node (ref "R9") (pin "2") (pinfunction "2_2") (pintype "passive"))
      (node (ref "T9") (pin "2") (pinfunction "D_2") (pintype "passive"))
      (node (ref "T9") (pin "4") (pinfunction "D_4") (pintype "passive"))
    )
    (net (code "15") (name "Net-(10-P)") (class "Default")
      (node (ref "10") (pin "1") (pinfunction "P_1") (pintype "passive"))
      (node (ref "R10") (pin "2") (pinfunction "2_2") (pintype "passive"))
      (node (ref "T10") (pin "2") (pinfunction "D_2") (pintype "passive"))
      (node (ref "T10") (pin "4") (pinfunction "D_4") (pintype "passive"))
    )
    (net (code "16") (name "Net-(11-P)") (class "Default")
      (node (ref "11") (pin "1") (pinfunction "P_1") (pintype "passive"))
      (node (ref "R11") (pin "2") (pinfunction "2_2") (pintype "passive"))
      (node (ref "T11") (pin "2") (pinfunction "D_2") (pintype "passive"))
      (node (ref "T11") (pin "4") (pinfunction "D_4") (pintype "passive"))
    )
    (net (code "17") (name "Net-(12-P)") (class "Default")
      (node (ref "12") (pin "1") (pinfunction "P_1") (pintype "passive"))
      (node (ref "R12") (pin "2") (pinfunction "2_2") (pintype "passive"))
      (node (ref "T12") (pin "2") (pinfunction "D_2") (pintype "passive"))
      (node (ref "T12") (pin "4") (pinfunction "D_4") (pintype "passive"))
    )
    (net (code "18") (name "Net-(13-P)") (class "Default")
      (node (ref "13") (pin "1") (pinfunction "P_1") (pintype "passive"))
      (node (ref "R13") (pin "2") (pinfunction "2_2") (pintype "passive"))
      (node (ref "T13") (pin "2") (pinfunction "D_2") (pintype "passive"))
      (node (ref "T13") (pin "4") (pinfunction "D_4") (pintype "passive"))
    )
    (net (code "19") (name "Net-(14-P)") (class "Default")
      (node (ref "14") (pin "1") (pinfunction "P_1") (pintype "passive"))
      (node (ref "R14") (pin "2") (pinfunction "2_2") (pintype "passive"))
      (node (ref "T14") (pin "2") (pinfunction "D_2") (pintype "passive"))
      (node (ref "T14") (pin "4") (pinfunction "D_4") (pintype "passive"))
    )
    (net (code "20") (name "Net-(15-P)") (class "Default")
      (node (ref "15") (pin "1") (pinfunction "P_1") (pintype "passive"))
      (node (ref "R15") (pin "2") (pinfunction "2_2") (pintype "passive"))
      (node (ref "T15") (pin "2") (pinfunction "D_2") (pintype "passive"))
      (node (ref "T15") (pin "4") (pinfunction "D_4") (pintype "passive"))
    )
    (net (code "21") (name "Net-(16-P)") (class "Default")
      (node (ref "16") (pin "1") (pinfunction "P_1") (pintype "passive"))
      (node (ref "R16") (pin "2") (pinfunction "2_2") (pintype "passive"))
      (node (ref "T16") (pin "2") (pinfunction "D_2") (pintype "passive"))
      (node (ref "T16") (pin "4") (pinfunction "D_4") (pintype "passive"))
    )
    (net (code "22") (name "Net-(17-P)") (class "Default")
      (node (ref "17") (pin "1") (pinfunction "P_1") (pintype "passive"))
      (node (ref "R17") (pin "2") (pinfunction "2_2") (pintype "passive"))
      (node (ref "T17") (pin "2") (pinfunction "D_2") (pintype "passive"))
      (node (ref "T17") (pin "4") (pinfunction "D_4") (pintype "passive"))
    )
    (net (code "23") (name "Net-(18-P)") (class "Default")
      (node (ref "18") (pin "1") (pinfunction "P_1") (pintype "passive"))
      (node (ref "R18") (pin "2") (pinfunction "2_2") (pintype "passive"))
      (node (ref "T18") (pin "2") (pinfunction "D_2") (pintype "passive"))
      (node (ref "T18") (pin "4") (pinfunction "D_4") (pintype "passive"))
    )
    (net (code "24") (name "Net-(19-P)") (class "Default")
      (node (ref "19") (pin "1") (pinfunction "P_1") (pintype "passive"))
      (node (ref "R19") (pin "2") (pinfunction "2_2") (pintype "passive"))
      (node (ref "T19") (pin "2") (pinfunction "D_2") (pintype "passive"))
      (node (ref "T19") (pin "4") (pinfunction "D_4") (pintype "passive"))
    )
    (net (code "25") (name "Net-(20-P)") (class "Default")
      (node (ref "20") (pin "1") (pinfunction "P_1") (pintype "passive"))
      (node (ref "R20") (pin "2") (pinfunction "2_2") (pintype "passive"))
      (node (ref "T20") (pin "2") (pinfunction "D_2") (pintype "passive"))
      (node (ref "T20") (pin "4") (pinfunction "D_4") (pintype "passive"))
    )
    (net (code "26") (name "Net-(21-P)") (class "Default")
      (node (ref "21") (pin "1") (pinfunction "P_1") (pintype "passive"))
      (node (ref "R21") (pin "2") (pinfunction "2_2") (pintype "passive"))
      (node (ref "T21") (pin "2") (pinfunction "D_2") (pintype "passive"))
      (node (ref "T21") (pin "4") (pinfunction "D_4") (pintype "passive"))
    )
    (net (code "27") (name "Net-(22-P)") (class "Default")
      (node (ref "22") (pin "1") (pinfunction "P_1") (pintype "passive"))
      (node (ref "R22") (pin "2") (pinfunction "2_2") (pintype "passive"))
      (node (ref "T22") (pin "2") (pinfunction "D_2") (pintype "passive"))
      (node (ref "T22") (pin "4") (pinfunction "D_4") (pintype "passive"))
    )
    (net (code "28") (name "Net-(23-P)") (class "Default")
      (node (ref "23") (pin "1") (pinfunction "P_1") (pintype "passive"))
      (node (ref "R23") (pin "2") (pinfunction "2_2") (pintype "passive"))
      (node (ref "T23") (pin "2") (pinfunction "D_2") (pintype "passive"))
      (node (ref "T23") (pin "4") (pinfunction "D_4") (pintype "passive"))
    )
    (net (code "29") (name "Net-(24-P)") (class "Default")
      (node (ref "24") (pin "1") (pinfunction "P_1") (pintype "passive"))
      (node (ref "R24") (pin "2") (pinfunction "2_2") (pintype "passive"))
      (node (ref "T24") (pin "2") (pinfunction "D_2") (pintype "passive"))
      (node (ref "T24") (pin "4") (pinfunction "D_4") (pintype "passive"))
    )
    (net (code "30") (name "Net-(25-P)") (class "Default")
      (node (ref "25") (pin "1") (pinfunction "P_1") (pintype "passive"))
      (node (ref "R25") (pin "2") (pinfunction "2_2") (pintype "passive"))
      (node (ref "T25") (pin "2") (pinfunction "D_2") (pintype "passive"))
      (node (ref "T25") (pin "4") (pinfunction "D_4") (pintype "passive"))
    )
    (net (code "31") (name "Net-(26-P)") (class "Default")
      (node (ref "26") (pin "1") (pinfunction "P_1") (pintype "passive"))
      (node (ref "R26") (pin "2") (pinfunction "2_2") (pintype "passive"))
      (node (ref "T26") (pin "2") (pinfunction "D_2") (pintype "passive"))
      (node (ref "T26") (pin "4") (pinfunction "D_4") (pintype "passive"))
    )
    (net (code "32") (name "Net-(27-P)") (class "Default")
      (node (ref "27") (pin "1") (pinfunction "P_1") (pintype "passive"))
      (node (ref "R27") (pin "2") (pinfunction "2_2") (pintype "passive"))
      (node (ref "T27") (pin "2") (pinfunction "D_2") (pintype "passive"))
      (node (ref "T27") (pin "4") (pinfunction "D_4") (pintype "passive"))
    )
    (net (code "33") (name "Net-(D1-Pad+)") (class "Default")
      (node (ref "D1") (pin "+") (pinfunction "+_+") (pintype "passive"))
      (node (ref "X3") (pin "7") (pinfunction "7_7") (pintype "passive"))
    )
    (net (code "34") (name "Net-(D4-Pad+)") (class "Default")
      (node (ref "D4") (pin "+") (pinfunction "+_+") (pintype "passive"))
      (node (ref "X1") (pin "7") (pinfunction "7_7") (pintype "passive"))
    )
    (net (code "35") (name "Net-(D7-Pad+)") (class "Default")
      (node (ref "D7") (pin "+") (pinfunction "+_+") (pintype "passive"))
      (node (ref "X2") (pin "7") (pinfunction "7_7") (pintype "passive"))
    )
    (net (code "36") (name "Net-(D10-Pad+)") (class "Default")
      (node (ref "D10") (pin "+") (pinfunction "+_+") (pintype "passive"))
      (node (ref "X4") (pin "7") (pinfunction "7_7") (pintype "passive"))
    )
    (net (code "37") (name "Net-(D13-Pad+)") (class "Default")
      (node (ref "D13") (pin "+") (pinfunction "+_+") (pintype "passive"))
      (node (ref "X5") (pin "7") (pinfunction "7_7") (pintype "passive"))
    )
    (net (code "38") (name "Net-(D16-Pad+)") (class "Default")
      (node (ref "D16") (pin "+") (pinfunction "+_+") (pintype "passive"))
      (node (ref "X6") (pin "7") (pinfunction "7_7") (pintype "passive"))
    )
    (net (code "39") (name "Net-(D19-Pad+)") (class "Default")
      (node (ref "D19") (pin "+") (pinfunction "+_+") (pintype "passive"))
      (node (ref "X7") (pin "7") (pinfunction "7_7") (pintype "passive"))
    )
    (net (code "40") (name "Net-(D22-Pad+)") (class "Default")
      (node (ref "D22") (pin "+") (pinfunction "+_+") (pintype "passive"))
      (node (ref "X8") (pin "7") (pinfunction "7_7") (pintype "passive"))
    )
    (net (code "41") (name "Net-(D25-Pad+)") (class "Default")
      (node (ref "D25") (pin "+") (pinfunction "+_+") (pintype "passive"))
      (node (ref "X9") (pin "7") (pinfunction "7_7") (pintype "passive"))
    )
    (net (code "42") (name "Net-(T1-G)") (class "Default")
      (node (ref "D1") (pin "-") (pinfunction "-_-") (pintype "passive"))
      (node (ref "T1") (pin "1") (pinfunction "G_1") (pintype "passive"))
    )
    (net (code "43") (name "Net-(T2-G)") (class "Default")
      (node (ref "D2") (pin "-") (pinfunction "-_-") (pintype "passive"))
      (node (ref "T2") (pin "1") (pinfunction "G_1") (pintype "passive"))
    )
    (net (code "44") (name "Net-(T3-G)") (class "Default")
      (node (ref "D3") (pin "-") (pinfunction "-_-") (pintype "passive"))
      (node (ref "T3") (pin "1") (pinfunction "G_1") (pintype "passive"))
    )
    (net (code "45") (name "Net-(T4-G)") (class "Default")
      (node (ref "D4") (pin "-") (pinfunction "-_-") (pintype "passive"))
      (node (ref "T4") (pin "1") (pinfunction "G_1") (pintype "passive"))
    )
    (net (code "46") (name "Net-(T5-G)") (class "Default")
      (node (ref "D5") (pin "-") (pinfunction "-_-") (pintype "passive"))
      (node (ref "T5") (pin "1") (pinfunction "G_1") (pintype "passive"))
    )
    (net (code "47") (name "Net-(T6-G)") (class "Default")
      (node (ref "D6") (pin "-") (pinfunction "-_-") (pintype "passive"))
      (node (ref "T6") (pin "1") (pinfunction "G_1") (pintype "passive"))
    )
    (net (code "48") (name "Net-(T7-G)") (class "Default")
      (node (ref "D7") (pin "-") (pinfunction "-_-") (pintype "passive"))
      (node (ref "T7") (pin "1") (pinfunction "G_1") (pintype "passive"))
    )
    (net (code "49") (name "Net-(T8-G)") (class "Default")
      (node (ref "D8") (pin "-") (pinfunction "-_-") (pintype "passive"))
      (node (ref "T8") (pin "1") (pinfunction "G_1") (pintype "passive"))
    )
    (net (code "50") (name "Net-(T9-G)") (class "Default")
      (node (ref "D9") (pin "-") (pinfunction "-_-") (pintype "passive"))
      (node (ref "T9") (pin "1") (pinfunction "G_1") (pintype "passive"))
    )
    (net (code "51") (name "Net-(T10-G)") (class "Default")
      (node (ref "D10") (pin "-") (pinfunction "-_-") (pintype "passive"))
      (node (ref "T10") (pin "1") (pinfunction "G_1") (pintype "passive"))
    )
    (net (code "52") (name "Net-(T11-G)") (class "Default")
      (node (ref "D11") (pin "-") (pinfunction "-_-") (pintype "passive"))
      (node (ref "T11") (pin "1") (pinfunction "G_1") (pintype "passive"))
    )
    (net (code "53") (name "Net-(T12-G)") (class "Default")
      (node (ref "D12") (pin "-") (pinfunction "-_-") (pintype "passive"))
      (node (ref "T12") (pin "1") (pinfunction "G_1") (pintype "passive"))
    )
    (net (code "54") (name "Net-(T13-G)") (class "Default")
      (node (ref "D13") (pin "-") (pinfunction "-_-") (pintype "passive"))
      (node (ref "T13") (pin "1") (pinfunction "G_1") (pintype "passive"))
    )
    (net (code "55") (name "Net-(T14-G)") (class "Default")
      (node (ref "D14") (pin "-") (pinfunction "-_-") (pintype "passive"))
      (node (ref "T14") (pin "1") (pinfunction "G_1") (pintype "passive"))
    )
    (net (code "56") (name "Net-(T15-G)") (class "Default")
      (node (ref "D15") (pin "-") (pinfunction "-_-") (pintype "passive"))
      (node (ref "T15") (pin "1") (pinfunction "G_1") (pintype "passive"))
    )
    (net (code "57") (name "Net-(T16-G)") (class "Default")
      (node (ref "D16") (pin "-") (pinfunction "-_-") (pintype "passive"))
      (node (ref "T16") (pin "1") (pinfunction "G_1") (pintype "passive"))
    )
    (net (code "58") (name "Net-(T17-G)") (class "Default")
      (node (ref "D17") (pin "-") (pinfunction "-_-") (pintype "passive"))
      (node (ref "T17") (pin "1") (pinfunction "G_1") (pintype "passive"))
    )
    (net (code "59") (name "Net-(T18-G)") (class "Default")
      (node (ref "D18") (pin "-") (pinfunction "-_-") (pintype "passive"))
      (node (ref "T18") (pin "1") (pinfunction "G_1") (pintype "passive"))
    )
    (net (code "60") (name "Net-(T19-G)") (class "Default")
      (node (ref "D19") (pin "-") (pinfunction "-_-") (pintype "passive"))
      (node (ref "T19") (pin "1") (pinfunction "G_1") (pintype "passive"))
    )
    (net (code "61") (name "Net-(T20-G)") (class "Default")
      (node (ref "D20") (pin "-") (pinfunction "-_-") (pintype "passive"))
      (node (ref "T20") (pin "1") (pinfunction "G_1") (pintype "passive"))
    )
    (net (code "62") (name "Net-(T21-G)") (class "Default")
      (node (ref "D21") (pin "-") (pinfunction "-_-") (pintype "passive"))
      (node (ref "T21") (pin "1") (pinfunction "G_1") (pintype "passive"))
    )
    (net (code "63") (name "Net-(T22-G)") (class "Default")
      (node (ref "D22") (pin "-") (pinfunction "-_-") (pintype "passive"))
      (node (ref "T22") (pin "1") (pinfunction "G_1") (pintype "passive"))
    )
    (net (code "64") (name "Net-(T23-G)") (class "Default")
      (node (ref "D23") (pin "-") (pinfunction "-_-") (pintype "passive"))
      (node (ref "T23") (pin "1") (pinfunction "G_1") (pintype "passive"))
    )
    (net (code "65") (name "Net-(T24-G)") (class "Default")
      (node (ref "D24") (pin "-") (pinfunction "-_-") (pintype "passive"))
      (node (ref "T24") (pin "1") (pinfunction "G_1") (pintype "passive"))
    )
    (net (code "66") (name "Net-(T25-G)") (class "Default")
      (node (ref "D25") (pin "-") (pinfunction "-_-") (pintype "passive"))
      (node (ref "T25") (pin "1") (pinfunction "G_1") (pintype "passive"))
    )
    (net (code "67") (name "Net-(T26-G)") (class "Default")
      (node (ref "D26") (pin "-") (pinfunction "-_-") (pintype "passive"))
      (node (ref "T26") (pin "1") (pinfunction "G_1") (pintype "passive"))
    )
    (net (code "68") (name "Net-(T27-G)") (class "Default")
      (node (ref "D27") (pin "-") (pinfunction "-_-") (pintype "passive"))
      (node (ref "T27") (pin "1") (pinfunction "G_1") (pintype "passive"))
    )
    (net (code "69") (name "RTS") (class "Default")
      (node (ref "D11") (pin "+") (pinfunction "+_+") (pintype "passive"))
      (node (ref "D14") (pin "+") (pinfunction "+_+") (pintype "passive"))
      (node (ref "D17") (pin "+") (pinfunction "+_+") (pintype "passive"))
      (node (ref "D2") (pin "+") (pinfunction "+_+") (pintype "passive"))
      (node (ref "D20") (pin "+") (pinfunction "+_+") (pintype "passive"))
      (node (ref "D23") (pin "+") (pinfunction "+_+") (pintype "passive"))
      (node (ref "D26") (pin "+") (pinfunction "+_+") (pintype "passive"))
      (node (ref "D5") (pin "+") (pinfunction "+_+") (pintype "passive"))
      (node (ref "D8") (pin "+") (pinfunction "+_+") (pintype "passive"))
      (node (ref "X1") (pin "3") (pinfunction "3_3") (pintype "passive"))
      (node (ref "X2") (pin "3") (pinfunction "3_3") (pintype "passive"))
      (node (ref "X3") (pin "3") (pinfunction "3_3") (pintype "passive"))
      (node (ref "X4") (pin "3") (pinfunction "3_3") (pintype "passive"))
      (node (ref "X5") (pin "3") (pinfunction "3_3") (pintype "passive"))
      (node (ref "X6") (pin "3") (pinfunction "3_3") (pintype "passive"))
      (node (ref "X7") (pin "3") (pinfunction "3_3") (pintype "passive"))
      (node (ref "X8") (pin "3") (pinfunction "3_3") (pintype "passive"))
      (node (ref "X9") (pin "3") (pinfunction "3_3") (pintype "passive"))
    )
    (net (code "70") (name "unconnected-(X1-Pad2)") (class "Default")
      (node (ref "X1") (pin "2") (pinfunction "2_2") (pintype "passive"))
    )
    (net (code "71") (name "unconnected-(X1-Pad9)") (class "Default")
      (node (ref "X1") (pin "9") (pinfunction "9_9") (pintype "passive"))
    )
    (net (code "72") (name "unconnected-(X2-Pad2)") (class "Default")
      (node (ref "X2") (pin "2") (pinfunction "2_2") (pintype "passive"))
    )
    (net (code "73") (name "unconnected-(X2-Pad9)") (class "Default")
      (node (ref "X2") (pin "9") (pinfunction "9_9") (pintype "passive"))
    )
    (net (code "74") (name "unconnected-(X3-Pad2)") (class "Default")
      (node (ref "X3") (pin "2") (pinfunction "2_2") (pintype "passive"))
    )
    (net (code "75") (name "unconnected-(X3-Pad9)") (class "Default")
      (node (ref "X3") (pin "9") (pinfunction "9_9") (pintype "passive"))
    )
    (net (code "76") (name "unconnected-(X4-Pad2)") (class "Default")
      (node (ref "X4") (pin "2") (pinfunction "2_2") (pintype "passive"))
    )
    (net (code "77") (name "unconnected-(X4-Pad9)") (class "Default")
      (node (ref "X4") (pin "9") (pinfunction "9_9") (pintype "passive"))
    )
    (net (code "78") (name "unconnected-(X5-Pad2)") (class "Default")
      (node (ref "X5") (pin "2") (pinfunction "2_2") (pintype "passive"))
    )
    (net (code "79") (name "unconnected-(X5-Pad9)") (class "Default")
      (node (ref "X5") (pin "9") (pinfunction "9_9") (pintype "passive"))
    )
    (net (code "80") (name "unconnected-(X6-Pad2)") (class "Default")
      (node (ref "X6") (pin "2") (pinfunction "2_2") (pintype "passive"))
    )
    (net (code "81") (name "unconnected-(X6-Pad9)") (class "Default")
      (node (ref "X6") (pin "9") (pinfunction "9_9") (pintype "passive"))
    )
    (net (code "82") (name "unconnected-(X7-Pad2)") (class "Default")
      (node (ref "X7") (pin "2") (pinfunction "2_2") (pintype "passive"))
    )
    (net (code "83") (name "unconnected-(X7-Pad9)") (class "Default")
      (node (ref "X7") (pin "9") (pinfunction "9_9") (pintype "passive"))
    )
    (net (code "84") (name "unconnected-(X8-Pad2)") (class "Default")
      (node (ref "X8") (pin "2") (pinfunction "2_2") (pintype "passive"))
    )
    (net (code "85") (name "unconnected-(X8-Pad9)") (class "Default")
      (node (ref "X8") (pin "9") (pinfunction "9_9") (pintype "passive"))
    )
    (net (code "86") (name "unconnected-(X9-Pad2)") (class "Default")
      (node (ref "X9") (pin "2") (pinfunction "2_2") (pintype "passive"))
    )
    (net (code "87") (name "unconnected-(X9-Pad9)") (class "Default")
      (node (ref "X9") (pin "9") (pinfunction "9_9") (pintype "passive"))
    )
  )
)
